# power.net
KiCad netlist of a schematic drawn in Altium Designer
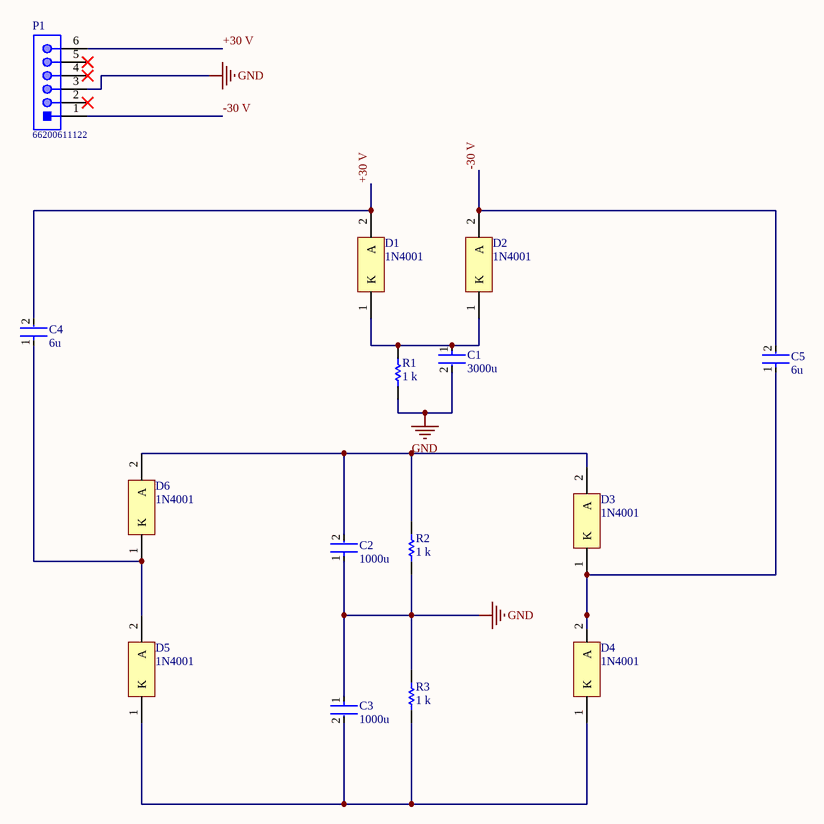
[diagram p0: power.SchDoc]

(export (version "E")
  (design (tool "Eeschema 10.0.6"))
  (components
    (comp (ref "C1")
      (value "3000u")
      (footprint "FP-VY1472M63Y5UQ6TV0-MFG")
      (description "CAP CER 4700PF 760VAC Y5U RADIAL")
      (fields (field (name "TOLERANCE") "20%") (field (name "VOLTAGE") "500V"))
      (libsource (lib "Altium Content Vault") (part "11868f565c42a9108669ba33697ecf6"))
    )
    (comp (ref "C2")
      (value "1000u")
      (footprint "FP-VY1472M63Y5UQ6TV0-MFG")
      (description "CAP CER 4700PF 760VAC Y5U RADIAL")
      (fields (field (name "TOLERANCE") "20%") (field (name "VOLTAGE") "500V"))
      (libsource (lib "Altium Content Vault") (part "11868f565c42a9108669ba33697ecf6"))
    )
    (comp (ref "C3")
      (value "1000u")
      (footprint "FP-VY1472M63Y5UQ6TV0-MFG")
      (description "CAP CER 4700PF 760VAC Y5U RADIAL")
      (fields (field (name "TOLERANCE") "20%") (field (name "VOLTAGE") "500V"))
      (libsource (lib "Altium Content Vault") (part "11868f565c42a9108669ba33697ecf6"))
    )
    (comp (ref "C4")
      (value "6u")
      (footprint "FP-VY1472M63Y5UQ6TV0-MFG")
      (description "CAP CER 4700PF 760VAC Y5U RADIAL")
      (fields (field (name "TOLERANCE") "20%") (field (name "VOLTAGE") "500V"))
      (libsource (lib "Altium Content Vault") (part "11868f565c42a9108669ba33697ecf6"))
    )
    (comp (ref "C5")
      (value "6u")
      (footprint "FP-VY1472M63Y5UQ6TV0-MFG")
      (description "CAP CER 4700PF 760VAC Y5U RADIAL")
      (fields (field (name "TOLERANCE") "20%") (field (name "VOLTAGE") "500V"))
      (libsource (lib "Altium Content Vault") (part "11868f565c42a9108669ba33697ecf6"))
    )
    (comp (ref "D1")
      (value "1N4001")
      (footprint "ONSC-AXIAL_LEAD-2-59-10_P")
      (description "Standard Recovery Rectifier, 2-Pin Axial_Lead, Pb-Free, Bulk Bag")
      (fields (field (name "MANUFACTURER") "On Semiconductor"))
      (libsource (lib "Altium Content Vault") (part "ONSC-D-K1A2-2_A"))
    )
    (comp (ref "D2")
      (value "1N4001")
      (footprint "ONSC-AXIAL_LEAD-2-59-10_P")
      (description "Standard Recovery Rectifier, 2-Pin Axial_Lead, Pb-Free, Bulk Bag")
      (fields (field (name "MANUFACTURER") "On Semiconductor"))
      (libsource (lib "Altium Content Vault") (part "ONSC-D-K1A2-2_A"))
    )
    (comp (ref "D3")
      (value "1N4001")
      (footprint "ONSC-AXIAL_LEAD-2-59-10_P")
      (description "Standard Recovery Rectifier, 2-Pin Axial_Lead, Pb-Free, Bulk Bag")
      (fields (field (name "MANUFACTURER") "On Semiconductor"))
      (libsource (lib "Altium Content Vault") (part "ONSC-D-K1A2-2_A"))
    )
    (comp (ref "D4")
      (value "1N4001")
      (footprint "ONSC-AXIAL_LEAD-2-59-10_P")
      (description "Standard Recovery Rectifier, 2-Pin Axial_Lead, Pb-Free, Bulk Bag")
      (fields (field (name "MANUFACTURER") "On Semiconductor"))
      (libsource (lib "Altium Content Vault") (part "ONSC-D-K1A2-2_A"))
    )
    (comp (ref "D5")
      (value "1N4001")
      (footprint "ONSC-AXIAL_LEAD-2-59-10_P")
      (description "Standard Recovery Rectifier, 2-Pin Axial_Lead, Pb-Free, Bulk Bag")
      (fields (field (name "MANUFACTURER") "On Semiconductor"))
      (libsource (lib "Altium Content Vault") (part "ONSC-D-K1A2-2_A"))
    )
    (comp (ref "D6")
      (value "1N4001")
      (footprint "ONSC-AXIAL_LEAD-2-59-10_P")
      (description "Standard Recovery Rectifier, 2-Pin Axial_Lead, Pb-Free, Bulk Bag")
      (fields (field (name "MANUFACTURER") "On Semiconductor"))
      (libsource (lib "Altium Content Vault") (part "ONSC-D-K1A2-2_A"))
    )
    (comp (ref "P1")
      (value "66200611122")
      (footprint "66200611122")
      (description "THT Male Header WR-MPC3, Vertical, Single Row, pitch 3 mm, 6 pins")
      (fields (field (name "MANUFACTURER") "Wurth Elektronik") (field (name "PUBLISHER") "WurthElektronik"))
      (libsource (lib "Altium Content Vault") (part "WE-CN-1P-M-R6"))
    )
    (comp (ref "R1")
      (value "1 k")
      (footprint "OMTE-RES7X2.5-2")
      (fields
        (field (name "TOLERANCE") "±5%")
        (field (name "PARTNUMBER") "OD103JE")
        (field (name "MANUFACTURER") "Ohmite")
      )
      (libsource (lib "Altium Content Vault") (part "RES-2"))
    )
    (comp (ref "R2")
      (value "1 k")
      (footprint "OMTE-RES7X2.5-2")
      (fields
        (field (name "TOLERANCE") "±5%")
        (field (name "PARTNUMBER") "OD103JE")
        (field (name "MANUFACTURER") "Ohmite")
      )
      (libsource (lib "Altium Content Vault") (part "RES-2"))
    )
    (comp (ref "R3")
      (value "1 k")
      (footprint "OMTE-RES7X2.5-2")
      (fields
        (field (name "TOLERANCE") "±5%")
        (field (name "PARTNUMBER") "OD103JE")
        (field (name "MANUFACTURER") "Ohmite")
      )
      (libsource (lib "Altium Content Vault") (part "RES-2"))
    )
  )
  (nets
    (net (code "1") (name "/+30 V") (class "Default")
      (node (ref "C4") (pin "2") (pinfunction "2_2") (pintype "passive"))
      (node (ref "D1") (pin "2") (pinfunction "A_2") (pintype "passive"))
      (node (ref "P1") (pin "6") (pinfunction "6_6") (pintype "passive"))
    )
    (net (code "2") (name "/-30 V") (class "Default")
      (node (ref "C5") (pin "2") (pinfunction "2_2") (pintype "passive"))
      (node (ref "D2") (pin "2") (pinfunction "A_2") (pintype "passive"))
      (node (ref "P1") (pin "1") (pinfunction "1_1") (pintype "passive"))
    )
    (net (code "3") (name "GND") (class "Default")
      (node (ref "C1") (pin "2") (pinfunction "2_2") (pintype "passive"))
      (node (ref "C2") (pin "1") (pinfunction "1_1") (pintype "passive"))
      (node (ref "C3") (pin "1") (pinfunction "1_1") (pintype "passive"))
      (node (ref "P1") (pin "3") (pinfunction "3_3") (pintype "passive"))
      (node (ref "R1") (pin "1") (pinfunction "1_1") (pintype "passive"))
      (node (ref "R2") (pin "1") (pinfunction "1_1") (pintype "passive"))
      (node (ref "R3") (pin "2") (pinfunction "2_2") (pintype "passive"))
    )
    (net (code "4") (name "Net-(D1-K)") (class "Default")
      (node (ref "C1") (pin "1") (pinfunction "1_1") (pintype "passive"))
      (node (ref "D1") (pin "1") (pinfunction "K_1") (pintype "passive"))
      (node (ref "D2") (pin "1") (pinfunction "K_1") (pintype "passive"))
      (node (ref "R1") (pin "2") (pinfunction "2_2") (pintype "passive"))
    )
    (net (code "5") (name "Net-(D3-A)") (class "Default")
      (node (ref "C2") (pin "2") (pinfunction "2_2") (pintype "passive"))
      (node (ref "D3") (pin "2") (pinfunction "A_2") (pintype "passive"))
      (node (ref "D6") (pin "2") (pinfunction "A_2") (pintype "passive"))
      (node (ref "R2") (pin "2") (pinfunction "2_2") (pintype "passive"))
    )
    (net (code "6") (name "Net-(D3-K)") (class "Default")
      (node (ref "C5") (pin "1") (pinfunction "1_1") (pintype "passive"))
      (node (ref "D3") (pin "1") (pinfunction "K_1") (pintype "passive"))
      (node (ref "D4") (pin "2") (pinfunction "A_2") (pintype "passive"))
    )
    (net (code "7") (name "Net-(D4-K)") (class "Default")
      (node (ref "C3") (pin "2") (pinfunction "2_2") (pintype "passive"))
      (node (ref "D4") (pin "1") (pinfunction "K_1") (pintype "passive"))
      (node (ref "D5") (pin "1") (pinfunction "K_1") (pintype "passive"))
      (node (ref "R3") (pin "1") (pinfunction "1_1") (pintype "passive"))
    )
    (net (code "8") (name "Net-(D5-A)") (class "Default")
      (node (ref "C4") (pin "1") (pinfunction "1_1") (pintype "passive"))
      (node (ref "D5") (pin "2") (pinfunction "A_2") (pintype "passive"))
      (node (ref "D6") (pin "1") (pinfunction "K_1") (pintype "passive"))
    )
    (net (code "9") (name "unconnected-(P1-Pad2)") (class "Default")
      (node (ref "P1") (pin "2") (pinfunction "2_2") (pintype "passive+no_connect"))
    )
    (net (code "10") (name "unconnected-(P1-Pad4)") (class "Default")
      (node (ref "P1") (pin "4") (pinfunction "4_4") (pintype "passive+no_connect"))
    )
    (net (code "11") (name "unconnected-(P1-Pad5)") (class "Default")
      (node (ref "P1") (pin "5") (pinfunction "5_5") (pintype "passive+no_connect"))
    )
  )
)
